# FuelGauge.net
KiCad netlist of a schematic drawn in EAGLE
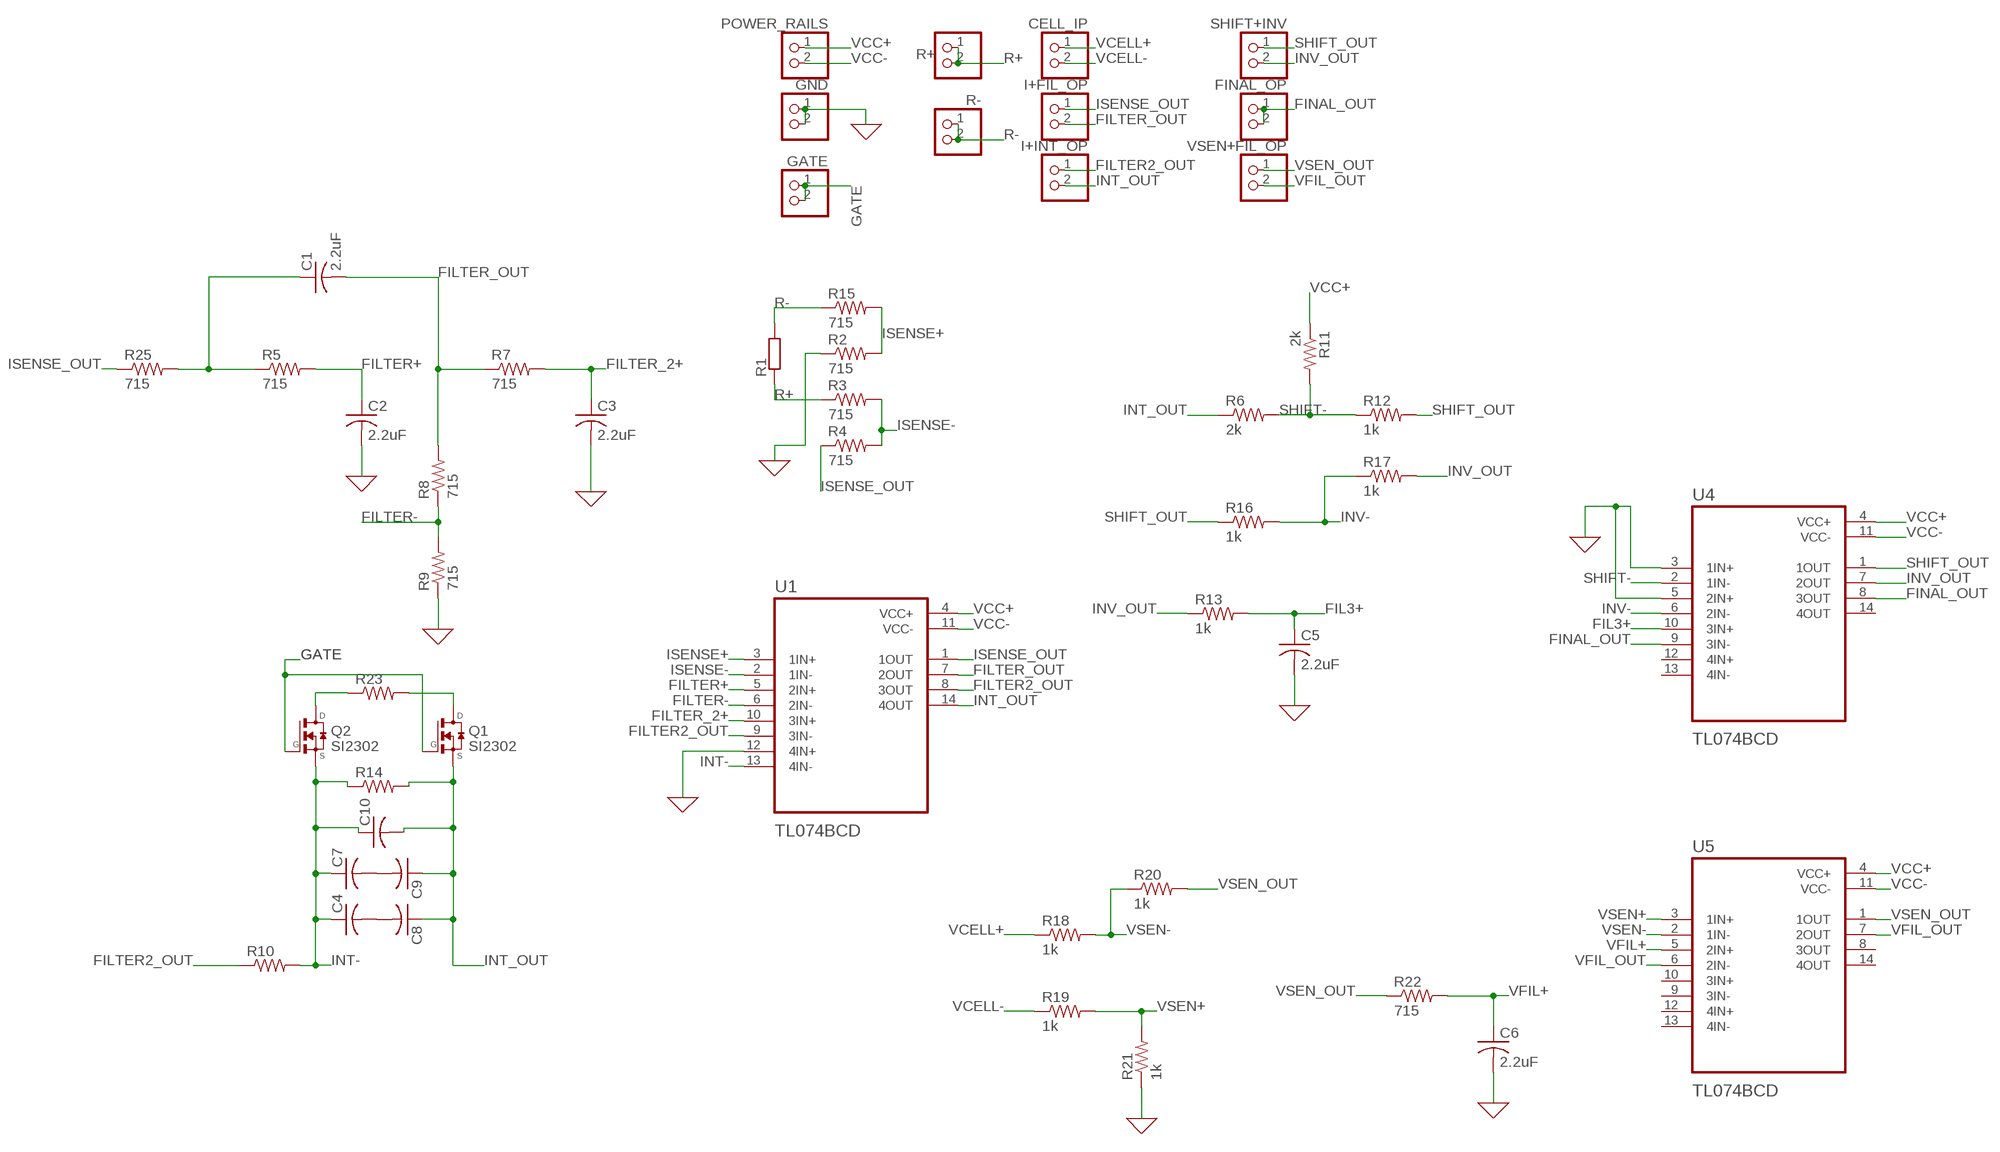
[diagram p0: schematic, sheet 1]

(export (version "E")
  (design (tool "Eeschema 10.0.6"))
  (components
    (comp (ref "C1")
      (value "2.2uF")
      (footprint "eagle-import:C0603")
      (libsource (lib "eagle-import") (part "C-USC0603"))
    )
    (comp (ref "C2")
      (value "2.2uF")
      (footprint "eagle-import:C0603")
      (libsource (lib "eagle-import") (part "C-USC0603"))
    )
    (comp (ref "C3")
      (value "2.2uF")
      (footprint "eagle-import:C0603")
      (libsource (lib "eagle-import") (part "C-USC0603"))
    )
    (comp (ref "C4")
      (value "C-US025-050X050")
      (footprint "eagle-import:C025-050X050")
      (libsource (lib "eagle-import") (part "C-US025-050X050"))
    )
    (comp (ref "C5")
      (value "2.2uF")
      (footprint "eagle-import:C0603")
      (libsource (lib "eagle-import") (part "C-USC0603"))
    )
    (comp (ref "C6")
      (value "2.2uF")
      (footprint "eagle-import:C0603")
      (libsource (lib "eagle-import") (part "C-USC0603"))
    )
    (comp (ref "C7")
      (value "C-US025-050X050")
      (footprint "eagle-import:C025-050X050")
      (libsource (lib "eagle-import") (part "C-US025-050X050"))
    )
    (comp (ref "C8")
      (value "C-US025-050X050")
      (footprint "eagle-import:C025-050X050")
      (libsource (lib "eagle-import") (part "C-US025-050X050"))
    )
    (comp (ref "C9")
      (value "C-US025-050X050")
      (footprint "eagle-import:C025-050X050")
      (libsource (lib "eagle-import") (part "C-US025-050X050"))
    )
    (comp (ref "C10")
      (value "C-USC0603")
      (footprint "eagle-import:C0603")
      (libsource (lib "eagle-import") (part "C-USC0603"))
    )
    (comp (ref "CELL_IP")
      (value "PINHD-1X2")
      (footprint "eagle-import:1X02")
      (libsource (lib "eagle-import") (part "PINHD-1X2"))
    )
    (comp (ref "FINAL_OP")
      (value "PINHD-1X2")
      (footprint "eagle-import:1X02")
      (libsource (lib "eagle-import") (part "PINHD-1X2"))
    )
    (comp (ref "GATE")
      (value "PINHD-1X2")
      (footprint "eagle-import:1X02")
      (libsource (lib "eagle-import") (part "PINHD-1X2"))
    )
    (comp (ref "GND")
      (value "PINHD-1X2")
      (footprint "eagle-import:1X02")
      (libsource (lib "eagle-import") (part "PINHD-1X2"))
    )
    (comp (ref "I+FIL_OP")
      (value "PINHD-1X2")
      (footprint "eagle-import:1X02")
      (libsource (lib "eagle-import") (part "PINHD-1X2"))
    )
    (comp (ref "I+INT_OP")
      (value "PINHD-1X2")
      (footprint "eagle-import:1X02")
      (libsource (lib "eagle-import") (part "PINHD-1X2"))
    )
    (comp (ref "POWER_RAILS")
      (value "PINHD-1X2")
      (footprint "eagle-import:1X02")
      (libsource (lib "eagle-import") (part "PINHD-1X2"))
    )
    (comp (ref "Q1")
      (value "SI2302")
      (footprint "eagle-import:SOT23")
      (fields (field (name "MF") "Vishay Siliconix"))
      (libsource (lib "eagle-import") (part "SI2302"))
    )
    (comp (ref "Q2")
      (value "SI2302")
      (footprint "eagle-import:SOT23")
      (fields (field (name "MF") "Vishay Siliconix"))
      (libsource (lib "eagle-import") (part "SI2302"))
    )
    (comp (ref "R+")
      (value "PINHD-1X2")
      (footprint "eagle-import:1X02")
      (libsource (lib "eagle-import") (part "PINHD-1X2"))
    )
    (comp (ref "R-")
      (value "PINHD-1X2")
      (footprint "eagle-import:1X02")
      (libsource (lib "eagle-import") (part "PINHD-1X2"))
    )
    (comp (ref "R1")
      (value "SMS-0")
      (footprint "eagle-import:SMS-0")
      (libsource (lib "eagle-import") (part "SMS-0"))
    )
    (comp (ref "R2")
      (value "715")
      (footprint "eagle-import:R0402")
      (libsource (lib "eagle-import") (part "R-US_R0402"))
    )
    (comp (ref "R3")
      (value "715")
      (footprint "eagle-import:R0402")
      (libsource (lib "eagle-import") (part "R-US_R0402"))
    )
    (comp (ref "R4")
      (value "715")
      (footprint "eagle-import:R0402")
      (libsource (lib "eagle-import") (part "R-US_R0402"))
    )
    (comp (ref "R5")
      (value "715")
      (footprint "eagle-import:R0402")
      (libsource (lib "eagle-import") (part "R-US_R0402"))
    )
    (comp (ref "R6")
      (value "2k")
      (footprint "eagle-import:R0402")
      (libsource (lib "eagle-import") (part "R-US_R0402"))
    )
    (comp (ref "R7")
      (value "715")
      (footprint "eagle-import:R0402")
      (libsource (lib "eagle-import") (part "R-US_R0402"))
    )
    (comp (ref "R8")
      (value "715")
      (footprint "eagle-import:R0402")
      (libsource (lib "eagle-import") (part "R-US_R0402"))
    )
    (comp (ref "R9")
      (value "715")
      (footprint "eagle-import:R0402")
      (libsource (lib "eagle-import") (part "R-US_R0402"))
    )
    (comp (ref "R10")
      (value "R-US_R0402")
      (footprint "eagle-import:R0402")
      (libsource (lib "eagle-import") (part "R-US_R0402"))
    )
    (comp (ref "R11")
      (value "2k")
      (footprint "eagle-import:R0402")
      (libsource (lib "eagle-import") (part "R-US_R0402"))
    )
    (comp (ref "R12")
      (value "1k")
      (footprint "eagle-import:R0402")
      (libsource (lib "eagle-import") (part "R-US_R0402"))
    )
    (comp (ref "R13")
      (value "1k")
      (footprint "eagle-import:R0402")
      (libsource (lib "eagle-import") (part "R-US_R0402"))
    )
    (comp (ref "R14")
      (value "R-US_R0402")
      (footprint "eagle-import:R0402")
      (libsource (lib "eagle-import") (part "R-US_R0402"))
    )
    (comp (ref "R15")
      (value "715")
      (footprint "eagle-import:R0402")
      (libsource (lib "eagle-import") (part "R-US_R0402"))
    )
    (comp (ref "R16")
      (value "1k")
      (footprint "eagle-import:R0402")
      (libsource (lib "eagle-import") (part "R-US_R0402"))
    )
    (comp (ref "R17")
      (value "1k")
      (footprint "eagle-import:R0402")
      (libsource (lib "eagle-import") (part "R-US_R0402"))
    )
    (comp (ref "R18")
      (value "1k")
      (footprint "eagle-import:R0402")
      (libsource (lib "eagle-import") (part "R-US_R0402"))
    )
    (comp (ref "R19")
      (value "1k")
      (footprint "eagle-import:R0402")
      (libsource (lib "eagle-import") (part "R-US_R0402"))
    )
    (comp (ref "R20")
      (value "1k")
      (footprint "eagle-import:R0402")
      (libsource (lib "eagle-import") (part "R-US_R0402"))
    )
    (comp (ref "R21")
      (value "1k")
      (footprint "eagle-import:R0402")
      (libsource (lib "eagle-import") (part "R-US_R0402"))
    )
    (comp (ref "R22")
      (value "715")
      (footprint "eagle-import:R0402")
      (libsource (lib "eagle-import") (part "R-US_R0402"))
    )
    (comp (ref "R23")
      (value "R-US_R0402")
      (footprint "eagle-import:R0402")
      (libsource (lib "eagle-import") (part "R-US_R0402"))
    )
    (comp (ref "R25")
      (value "715")
      (footprint "eagle-import:R0402")
      (libsource (lib "eagle-import") (part "R-US_R0402"))
    )
    (comp (ref "SHIFT+INV")
      (value "PINHD-1X2")
      (footprint "eagle-import:1X02")
      (libsource (lib "eagle-import") (part "PINHD-1X2"))
    )
    (comp (ref "U1")
      (value "TL074BCD")
      (footprint "eagle-import:SOIC127P600X175-14N")
      (fields (field (name "MF") "Texas Instruments"))
      (libsource (lib "eagle-import") (part "TL074BCD"))
    )
    (comp (ref "U4")
      (value "TL074BCD")
      (footprint "eagle-import:SOIC127P600X175-14N")
      (fields (field (name "MF") "Texas Instruments"))
      (libsource (lib "eagle-import") (part "TL074BCD"))
    )
    (comp (ref "U5")
      (value "TL074BCD")
      (footprint "eagle-import:SOIC127P600X175-14N")
      (fields (field (name "MF") "Texas Instruments"))
      (libsource (lib "eagle-import") (part "TL074BCD"))
    )
    (comp (ref "VSEN+FIL_OP")
      (value "PINHD-1X2")
      (footprint "eagle-import:1X02")
      (libsource (lib "eagle-import") (part "PINHD-1X2"))
    )
  )
  (nets
    (net (code "1") (name "/FIL3+") (class "Default")
      (node (ref "C5") (pin "1") (pinfunction "1_1") (pintype "passive"))
      (node (ref "R13") (pin "2") (pinfunction "2_2") (pintype "passive"))
      (node (ref "U4") (pin "10") (pinfunction "3IN+_10") (pintype "input"))
    )
    (net (code "2") (name "/FILTER+") (class "Default")
      (node (ref "C2") (pin "1") (pinfunction "1_1") (pintype "passive"))
      (node (ref "R5") (pin "2") (pinfunction "2_2") (pintype "passive"))
      (node (ref "U1") (pin "5") (pinfunction "2IN+_5") (pintype "input"))
    )
    (net (code "3") (name "/FILTER-") (class "Default")
      (node (ref "R8") (pin "1") (pinfunction "1_1") (pintype "passive"))
      (node (ref "R9") (pin "2") (pinfunction "2_2") (pintype "passive"))
      (node (ref "U1") (pin "6") (pinfunction "2IN-_6") (pintype "input"))
    )
    (net (code "4") (name "/FILTER2_OUT") (class "Default")
      (node (ref "I+INT_OP") (pin "1") (pinfunction "1_1") (pintype "passive"))
      (node (ref "R10") (pin "1") (pinfunction "1_1") (pintype "passive"))
      (node (ref "U1") (pin "8") (pinfunction "3OUT_8") (pintype "output"))
      (node (ref "U1") (pin "9") (pinfunction "3IN-_9") (pintype "input"))
    )
    (net (code "5") (name "/FILTER_2+") (class "Default")
      (node (ref "C3") (pin "1") (pinfunction "1_1") (pintype "passive"))
      (node (ref "R7") (pin "2") (pinfunction "2_2") (pintype "passive"))
      (node (ref "U1") (pin "10") (pinfunction "3IN+_10") (pintype "input"))
    )
    (net (code "6") (name "/FILTER_OUT") (class "Default")
      (node (ref "C1") (pin "2") (pinfunction "2_2") (pintype "passive"))
      (node (ref "I+FIL_OP") (pin "2") (pinfunction "2_2") (pintype "passive"))
      (node (ref "R7") (pin "1") (pinfunction "1_1") (pintype "passive"))
      (node (ref "R8") (pin "2") (pinfunction "2_2") (pintype "passive"))
      (node (ref "U1") (pin "7") (pinfunction "2OUT_7") (pintype "output"))
    )
    (net (code "7") (name "/FINAL_OUT") (class "Default")
      (node (ref "FINAL_OP") (pin "1") (pinfunction "1_1") (pintype "passive"))
      (node (ref "FINAL_OP") (pin "2") (pinfunction "2_2") (pintype "passive"))
      (node (ref "U4") (pin "8") (pinfunction "3OUT_8") (pintype "output"))
      (node (ref "U4") (pin "9") (pinfunction "3IN-_9") (pintype "input"))
    )
    (net (code "8") (name "/GATE") (class "Default")
      (node (ref "GATE") (pin "1") (pinfunction "1_1") (pintype "passive"))
      (node (ref "GATE") (pin "2") (pinfunction "2_2") (pintype "passive"))
      (node (ref "Q1") (pin "1") (pinfunction "G_1") (pintype "passive"))
      (node (ref "Q2") (pin "1") (pinfunction "G_1") (pintype "passive"))
    )
    (net (code "9") (name "/INT-") (class "Default")
      (node (ref "C10") (pin "1") (pinfunction "1_1") (pintype "passive"))
      (node (ref "C4") (pin "1") (pinfunction "1_1") (pintype "passive"))
      (node (ref "C7") (pin "1") (pinfunction "1_1") (pintype "passive"))
      (node (ref "Q2") (pin "2") (pinfunction "S_2") (pintype "passive"))
      (node (ref "R10") (pin "2") (pinfunction "2_2") (pintype "passive"))
      (node (ref "R14") (pin "1") (pinfunction "1_1") (pintype "passive"))
      (node (ref "U1") (pin "13") (pinfunction "4IN-_13") (pintype "input"))
    )
    (net (code "10") (name "/INT_OUT") (class "Default")
      (node (ref "I+INT_OP") (pin "2") (pinfunction "2_2") (pintype "passive"))
      (node (ref "R6") (pin "1") (pinfunction "1_1") (pintype "passive"))
      (node (ref "U1") (pin "14") (pinfunction "4OUT_14") (pintype "output"))
    )
    (net (code "11") (name "/INV-") (class "Default")
      (node (ref "R16") (pin "2") (pinfunction "2_2") (pintype "passive"))
      (node (ref "R17") (pin "1") (pinfunction "1_1") (pintype "passive"))
      (node (ref "U4") (pin "6") (pinfunction "2IN-_6") (pintype "input"))
    )
    (net (code "12") (name "/INV_OUT") (class "Default")
      (node (ref "R13") (pin "1") (pinfunction "1_1") (pintype "passive"))
      (node (ref "R17") (pin "2") (pinfunction "2_2") (pintype "passive"))
      (node (ref "SHIFT+INV") (pin "2") (pinfunction "2_2") (pintype "passive"))
      (node (ref "U4") (pin "7") (pinfunction "2OUT_7") (pintype "output"))
    )
    (net (code "13") (name "/ISENSE+") (class "Default")
      (node (ref "R15") (pin "2") (pinfunction "2_2") (pintype "passive"))
      (node (ref "R2") (pin "2") (pinfunction "2_2") (pintype "passive"))
      (node (ref "U1") (pin "3") (pinfunction "1IN+_3") (pintype "input"))
    )
    (net (code "14") (name "/ISENSE-") (class "Default")
      (node (ref "R3") (pin "2") (pinfunction "2_2") (pintype "passive"))
      (node (ref "R4") (pin "2") (pinfunction "2_2") (pintype "passive"))
      (node (ref "U1") (pin "2") (pinfunction "1IN-_2") (pintype "input"))
    )
    (net (code "15") (name "/ISENSE_OUT") (class "Default")
      (node (ref "I+FIL_OP") (pin "1") (pinfunction "1_1") (pintype "passive"))
      (node (ref "R25") (pin "1") (pinfunction "1_1") (pintype "passive"))
      (node (ref "R4") (pin "1") (pinfunction "1_1") (pintype "passive"))
      (node (ref "U1") (pin "1") (pinfunction "1OUT_1") (pintype "output"))
    )
    (net (code "16") (name "/R+") (class "Default")
      (node (ref "R+") (pin "1") (pinfunction "1_1") (pintype "passive"))
      (node (ref "R+") (pin "2") (pinfunction "2_2") (pintype "passive"))
      (node (ref "R1") (pin "2") (pinfunction "2_2") (pintype "passive"))
      (node (ref "R3") (pin "1") (pinfunction "1_1") (pintype "passive"))
    )
    (net (code "17") (name "/R-") (class "Default")
      (node (ref "R-") (pin "1") (pinfunction "1_1") (pintype "passive"))
      (node (ref "R-") (pin "2") (pinfunction "2_2") (pintype "passive"))
      (node (ref "R1") (pin "1") (pinfunction "1_1") (pintype "passive"))
      (node (ref "R15") (pin "1") (pinfunction "1_1") (pintype "passive"))
    )
    (net (code "18") (name "/SHIFT-") (class "Default")
      (node (ref "R11") (pin "2") (pinfunction "2_2") (pintype "passive"))
      (node (ref "R12") (pin "1") (pinfunction "1_1") (pintype "passive"))
      (node (ref "R6") (pin "2") (pinfunction "2_2") (pintype "passive"))
      (node (ref "U4") (pin "2") (pinfunction "1IN-_2") (pintype "input"))
    )
    (net (code "19") (name "/SHIFT_OUT") (class "Default")
      (node (ref "R12") (pin "2") (pinfunction "2_2") (pintype "passive"))
      (node (ref "R16") (pin "1") (pinfunction "1_1") (pintype "passive"))
      (node (ref "SHIFT+INV") (pin "1") (pinfunction "1_1") (pintype "passive"))
      (node (ref "U4") (pin "1") (pinfunction "1OUT_1") (pintype "output"))
    )
    (net (code "20") (name "/VCC+") (class "Default")
      (node (ref "POWER_RAILS") (pin "1") (pinfunction "1_1") (pintype "passive"))
      (node (ref "R11") (pin "1") (pinfunction "1_1") (pintype "passive"))
      (node (ref "U1") (pin "4") (pinfunction "VCC+_4") (pintype "power_in"))
      (node (ref "U4") (pin "4") (pinfunction "VCC+_4") (pintype "power_in"))
      (node (ref "U5") (pin "4") (pinfunction "VCC+_4") (pintype "power_in"))
    )
    (net (code "21") (name "/VCC-") (class "Default")
      (node (ref "POWER_RAILS") (pin "2") (pinfunction "2_2") (pintype "passive"))
      (node (ref "U1") (pin "11") (pinfunction "VCC-_11") (pintype "power_in"))
      (node (ref "U4") (pin "11") (pinfunction "VCC-_11") (pintype "power_in"))
      (node (ref "U5") (pin "11") (pinfunction "VCC-_11") (pintype "power_in"))
    )
    (net (code "22") (name "/VCELL+") (class "Default")
      (node (ref "CELL_IP") (pin "1") (pinfunction "1_1") (pintype "passive"))
      (node (ref "R18") (pin "1") (pinfunction "1_1") (pintype "passive"))
    )
    (net (code "23") (name "/VCELL-") (class "Default")
      (node (ref "CELL_IP") (pin "2") (pinfunction "2_2") (pintype "passive"))
      (node (ref "R19") (pin "1") (pinfunction "1_1") (pintype "passive"))
    )
    (net (code "24") (name "/VFIL+") (class "Default")
      (node (ref "C6") (pin "1") (pinfunction "1_1") (pintype "passive"))
      (node (ref "R22") (pin "2") (pinfunction "2_2") (pintype "passive"))
      (node (ref "U5") (pin "5") (pinfunction "2IN+_5") (pintype "input"))
    )
    (net (code "25") (name "/VFIL_OUT") (class "Default")
      (node (ref "U5") (pin "6") (pinfunction "2IN-_6") (pintype "input"))
      (node (ref "U5") (pin "7") (pinfunction "2OUT_7") (pintype "output"))
      (node (ref "VSEN+FIL_OP") (pin "2") (pinfunction "2_2") (pintype "passive"))
    )
    (net (code "26") (name "/VSEN+") (class "Default")
      (node (ref "R19") (pin "2") (pinfunction "2_2") (pintype "passive"))
      (node (ref "R21") (pin "2") (pinfunction "2_2") (pintype "passive"))
      (node (ref "U5") (pin "3") (pinfunction "1IN+_3") (pintype "input"))
    )
    (net (code "27") (name "/VSEN-") (class "Default")
      (node (ref "R18") (pin "2") (pinfunction "2_2") (pintype "passive"))
      (node (ref "R20") (pin "1") (pinfunction "1_1") (pintype "passive"))
      (node (ref "U5") (pin "2") (pinfunction "1IN-_2") (pintype "input"))
    )
    (net (code "28") (name "/VSEN_OUT") (class "Default")
      (node (ref "R20") (pin "2") (pinfunction "2_2") (pintype "passive"))
      (node (ref "R22") (pin "1") (pinfunction "1_1") (pintype "passive"))
      (node (ref "U5") (pin "1") (pinfunction "1OUT_1") (pintype "output"))
      (node (ref "VSEN+FIL_OP") (pin "1") (pinfunction "1_1") (pintype "passive"))
    )
    (net (code "29") (name "GND") (class "Default")
      (node (ref "C2") (pin "2") (pinfunction "2_2") (pintype "passive"))
      (node (ref "C3") (pin "2") (pinfunction "2_2") (pintype "passive"))
      (node (ref "C5") (pin "2") (pinfunction "2_2") (pintype "passive"))
      (node (ref "C6") (pin "2") (pinfunction "2_2") (pintype "passive"))
      (node (ref "GND") (pin "1") (pinfunction "1_1") (pintype "passive"))
      (node (ref "GND") (pin "2") (pinfunction "2_2") (pintype "passive"))
      (node (ref "R2") (pin "1") (pinfunction "1_1") (pintype "passive"))
      (node (ref "R21") (pin "1") (pinfunction "1_1") (pintype "passive"))
      (node (ref "R9") (pin "1") (pinfunction "1_1") (pintype "passive"))
      (node (ref "U1") (pin "12") (pinfunction "4IN+_12") (pintype "input"))
      (node (ref "U4") (pin "3") (pinfunction "1IN+_3") (pintype "input"))
      (node (ref "U4") (pin "5") (pinfunction "2IN+_5") (pintype "input"))
    )
    (net (code "30") (name "Net-(C1-Pad1)") (class "Default")
      (node (ref "C1") (pin "1") (pinfunction "1_1") (pintype "passive"))
      (node (ref "R25") (pin "2") (pinfunction "2_2") (pintype "passive"))
      (node (ref "R5") (pin "1") (pinfunction "1_1") (pintype "passive"))
    )
    (net (code "31") (name "Net-(C4-Pad2)") (class "Default")
      (node (ref "C4") (pin "2") (pinfunction "2_2") (pintype "passive"))
      (node (ref "C8") (pin "2") (pinfunction "2_2") (pintype "passive"))
    )
    (net (code "32") (name "Net-(C7-Pad2)") (class "Default")
      (node (ref "C7") (pin "2") (pinfunction "2_2") (pintype "passive"))
      (node (ref "C9") (pin "2") (pinfunction "2_2") (pintype "passive"))
    )
    (net (code "33") (name "Net-(Q1-D)") (class "Default")
      (node (ref "Q1") (pin "3") (pinfunction "D_3") (pintype "passive"))
      (node (ref "R23") (pin "2") (pinfunction "2_2") (pintype "passive"))
    )
    (net (code "34") (name "Net-(Q1-S)") (class "Default")
      (node (ref "C10") (pin "2") (pinfunction "2_2") (pintype "passive"))
      (node (ref "C8") (pin "1") (pinfunction "1_1") (pintype "passive"))
      (node (ref "C9") (pin "1") (pinfunction "1_1") (pintype "passive"))
      (node (ref "Q1") (pin "2") (pinfunction "S_2") (pintype "passive"))
      (node (ref "R14") (pin "2") (pinfunction "2_2") (pintype "passive"))
    )
    (net (code "35") (name "Net-(Q2-D)") (class "Default")
      (node (ref "Q2") (pin "3") (pinfunction "D_3") (pintype "passive"))
      (node (ref "R23") (pin "1") (pinfunction "1_1") (pintype "passive"))
    )
    (net (code "36") (name "unconnected-(U4-4IN+-Pad12)") (class "Default")
      (node (ref "U4") (pin "12") (pinfunction "4IN+_12") (pintype "input"))
    )
    (net (code "37") (name "unconnected-(U4-4IN--Pad13)") (class "Default")
      (node (ref "U4") (pin "13") (pinfunction "4IN-_13") (pintype "input"))
    )
    (net (code "38") (name "unconnected-(U4-4OUT-Pad14)") (class "Default")
      (node (ref "U4") (pin "14") (pinfunction "4OUT_14") (pintype "output"))
    )
    (net (code "39") (name "unconnected-(U5-3IN+-Pad10)") (class "Default")
      (node (ref "U5") (pin "10") (pinfunction "3IN+_10") (pintype "input"))
    )
    (net (code "40") (name "unconnected-(U5-3IN--Pad9)") (class "Default")
      (node (ref "U5") (pin "9") (pinfunction "3IN-_9") (pintype "input"))
    )
    (net (code "41") (name "unconnected-(U5-3OUT-Pad8)") (class "Default")
      (node (ref "U5") (pin "8") (pinfunction "3OUT_8") (pintype "output"))
    )
    (net (code "42") (name "unconnected-(U5-4IN+-Pad12)") (class "Default")
      (node (ref "U5") (pin "12") (pinfunction "4IN+_12") (pintype "input"))
    )
    (net (code "43") (name "unconnected-(U5-4IN--Pad13)") (class "Default")
      (node (ref "U5") (pin "13") (pinfunction "4IN-_13") (pintype "input"))
    )
    (net (code "44") (name "unconnected-(U5-4OUT-Pad14)") (class "Default")
      (node (ref "U5") (pin "14") (pinfunction "4OUT_14") (pintype "output"))
    )
  )
)
